# CO2Monitor_V0_3.net
KiCad netlist of a schematic drawn in EAGLE
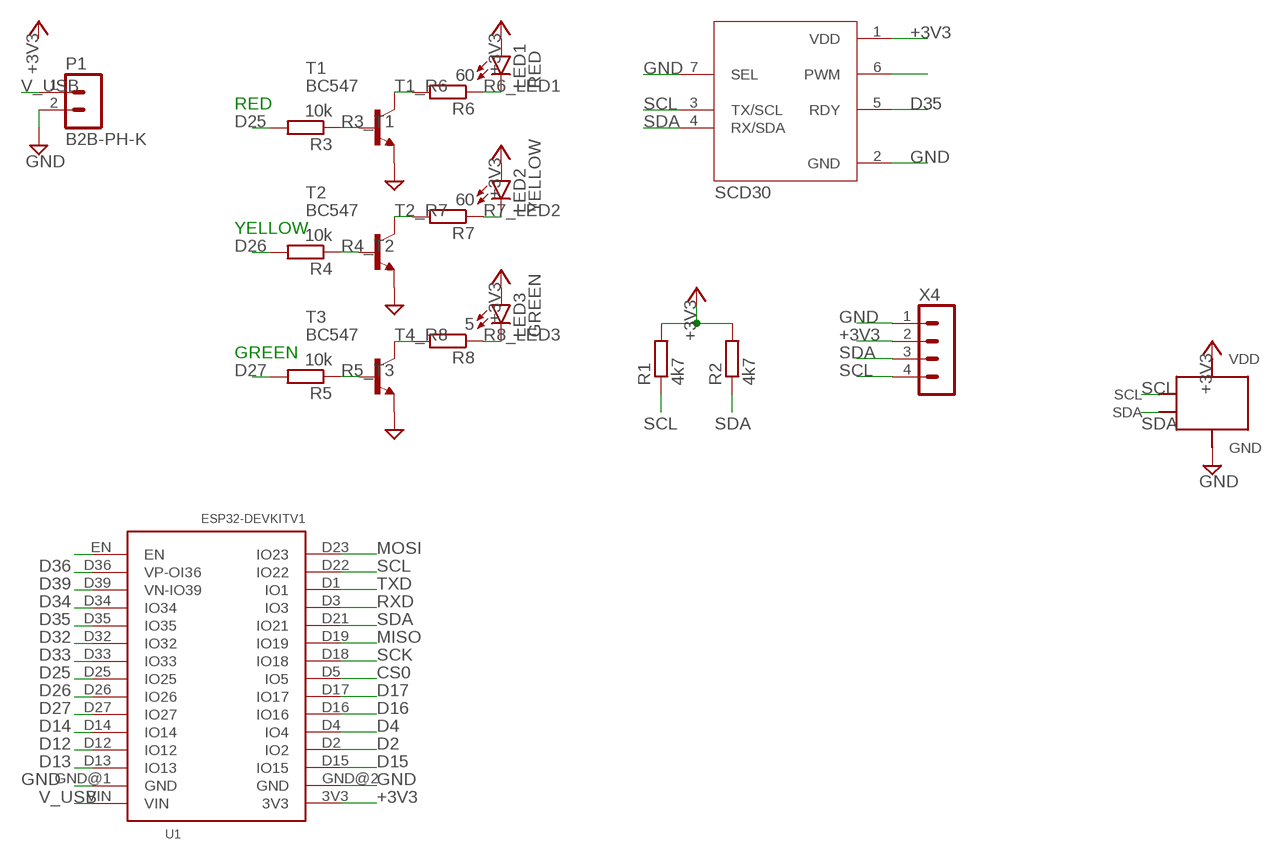
[diagram p0: schematic, sheet 1]

(export (version "E")
  (design (tool "Eeschema 10.0.6"))
  (components
    (comp (ref "LED1")
      (value "RED")
      (footprint "eagle-import:LED5MM")
      (libsource (lib "eagle-import") (part "LED5MM"))
    )
    (comp (ref "LED2")
      (value "YELLOW")
      (footprint "eagle-import:LED5MM")
      (libsource (lib "eagle-import") (part "LED5MM"))
    )
    (comp (ref "LED3")
      (value "GREEN")
      (footprint "eagle-import:LED5MM")
      (libsource (lib "eagle-import") (part "LED5MM"))
    )
    (comp (ref "P1")
      (value "B2B-PH-K")
      (footprint "eagle-import:B2B-PH-K")
      (libsource (lib "eagle-import") (part "B2B-PH-K"))
    )
    (comp (ref "R1")
      (value "4k7")
      (footprint "eagle-import:0207_10")
      (libsource (lib "eagle-import") (part "R-EU_0207/10"))
    )
    (comp (ref "R2")
      (value "4k7")
      (footprint "eagle-import:0207_10")
      (libsource (lib "eagle-import") (part "R-EU_0207/10"))
    )
    (comp (ref "R3")
      (value "10k")
      (footprint "eagle-import:0207_10")
      (libsource (lib "eagle-import") (part "R-EU_0207/10"))
    )
    (comp (ref "R4")
      (value "10k")
      (footprint "eagle-import:0207_10")
      (libsource (lib "eagle-import") (part "R-EU_0207/10"))
    )
    (comp (ref "R5")
      (value "10k")
      (footprint "eagle-import:0207_10")
      (libsource (lib "eagle-import") (part "R-EU_0207/10"))
    )
    (comp (ref "R6")
      (value "60")
      (footprint "eagle-import:0207_10")
      (libsource (lib "eagle-import") (part "R-EU_0207/10"))
    )
    (comp (ref "R7")
      (value "60")
      (footprint "eagle-import:0207_10")
      (libsource (lib "eagle-import") (part "R-EU_0207/10"))
    )
    (comp (ref "R8")
      (value "5")
      (footprint "eagle-import:0207_10")
      (libsource (lib "eagle-import") (part "R-EU_0207/10"))
    )
    (comp (ref "T1")
      (value "BC547")
      (footprint "eagle-import:TO92")
      (libsource (lib "eagle-import") (part "BC547"))
    )
    (comp (ref "T2")
      (value "BC547")
      (footprint "eagle-import:TO92")
      (libsource (lib "eagle-import") (part "BC547"))
    )
    (comp (ref "T3")
      (value "BC547")
      (footprint "eagle-import:TO92")
      (libsource (lib "eagle-import") (part "BC547"))
    )
    (comp (ref "U1")
      (value "ESP32DEVKITV1")
      (footprint "eagle-import:ESP32-DEVKITV1")
      (libsource (lib "eagle-import") (part "ESP32DEVKITV1"))
    )
    (comp (ref "U3")
      (value "SCD30")
      (footprint "eagle-import:MODULE_SCD30")
      (fields (field (name "MF") "Sensirion AG"))
      (libsource (lib "eagle-import") (part "SCD30"))
    )
    (comp (ref "X1")
      (value "1306_0.96\"")
      (footprint "eagle-import:1306_0.96_")
      (libsource (lib "eagle-import") (part "1306_0.96{dblquote}"))
    )
    (comp (ref "X4")
      (value "B4B-PH-K")
      (footprint "eagle-import:B4B-PH-K")
      (libsource (lib "eagle-import") (part "B4B-PH-K"))
    )
  )
  (nets
    (net (code "1") (name "+3V3") (class "Default")
      (node (ref "LED1") (pin "A") (pinfunction "A_A") (pintype "passive"))
      (node (ref "LED2") (pin "A") (pinfunction "A_A") (pintype "passive"))
      (node (ref "LED3") (pin "A") (pinfunction "A_A") (pintype "passive"))
      (node (ref "R1") (pin "2") (pinfunction "2_2") (pintype "passive"))
      (node (ref "R2") (pin "2") (pinfunction "2_2") (pintype "passive"))
      (node (ref "U1") (pin "3V3") (pinfunction "3V3_3V3") (pintype "bidirectional"))
      (node (ref "U3") (pin "1") (pinfunction "VDD_1") (pintype "power_in"))
      (node (ref "X1") (pin "VDD") (pinfunction "VDD_VDD") (pintype "bidirectional"))
      (node (ref "X4") (pin "2") (pinfunction "2_2") (pintype "passive"))
    )
    (net (code "2") (name "/CS0") (class "Default")
      (node (ref "U1") (pin "D5") (pinfunction "IO5_D5") (pintype "bidirectional"))
    )
    (net (code "3") (name "/D2") (class "Default")
      (node (ref "U1") (pin "D2") (pinfunction "IO2_D2") (pintype "bidirectional"))
    )
    (net (code "4") (name "/D4") (class "Default")
      (node (ref "U1") (pin "D4") (pinfunction "IO4_D4") (pintype "bidirectional"))
    )
    (net (code "5") (name "/D12") (class "Default")
      (node (ref "U1") (pin "D12") (pinfunction "IO12_D12") (pintype "bidirectional"))
    )
    (net (code "6") (name "/D13") (class "Default")
      (node (ref "U1") (pin "D13") (pinfunction "IO13_D13") (pintype "bidirectional"))
    )
    (net (code "7") (name "/D14") (class "Default")
      (node (ref "U1") (pin "D14") (pinfunction "IO14_D14") (pintype "bidirectional"))
    )
    (net (code "8") (name "/D15") (class "Default")
      (node (ref "U1") (pin "D15") (pinfunction "IO15_D15") (pintype "bidirectional"))
    )
    (net (code "9") (name "/D16") (class "Default")
      (node (ref "U1") (pin "D16") (pinfunction "IO16_D16") (pintype "bidirectional"))
    )
    (net (code "10") (name "/D17") (class "Default")
      (node (ref "U1") (pin "D17") (pinfunction "IO17_D17") (pintype "bidirectional"))
    )
    (net (code "11") (name "/D25") (class "Default")
      (node (ref "R3") (pin "2") (pinfunction "2_2") (pintype "passive"))
      (node (ref "U1") (pin "D25") (pinfunction "IO25_D25") (pintype "bidirectional"))
    )
    (net (code "12") (name "/D26") (class "Default")
      (node (ref "R4") (pin "2") (pinfunction "2_2") (pintype "passive"))
      (node (ref "U1") (pin "D26") (pinfunction "IO26_D26") (pintype "bidirectional"))
    )
    (net (code "13") (name "/D27") (class "Default")
      (node (ref "R5") (pin "2") (pinfunction "2_2") (pintype "passive"))
      (node (ref "U1") (pin "D27") (pinfunction "IO27_D27") (pintype "bidirectional"))
    )
    (net (code "14") (name "/D32") (class "Default")
      (node (ref "U1") (pin "D32") (pinfunction "IO32_D32") (pintype "bidirectional"))
    )
    (net (code "15") (name "/D33") (class "Default")
      (node (ref "U1") (pin "D33") (pinfunction "IO33_D33") (pintype "bidirectional"))
    )
    (net (code "16") (name "/D34") (class "Default")
      (node (ref "U1") (pin "D34") (pinfunction "IO34_D34") (pintype "bidirectional"))
    )
    (net (code "17") (name "/D35") (class "Default")
      (node (ref "U1") (pin "D35") (pinfunction "IO35_D35") (pintype "bidirectional"))
      (node (ref "U3") (pin "5") (pinfunction "RDY_5") (pintype "bidirectional"))
    )
    (net (code "18") (name "/D36") (class "Default")
      (node (ref "U1") (pin "D36") (pinfunction "VP-OI36_D36") (pintype "bidirectional"))
    )
    (net (code "19") (name "/D39") (class "Default")
      (node (ref "U1") (pin "D39") (pinfunction "VN-IO39_D39") (pintype "bidirectional"))
    )
    (net (code "20") (name "/MISO") (class "Default")
      (node (ref "U1") (pin "D19") (pinfunction "IO19_D19") (pintype "bidirectional"))
    )
    (net (code "21") (name "/MOSI") (class "Default")
      (node (ref "U1") (pin "D23") (pinfunction "IO23_D23") (pintype "bidirectional"))
    )
    (net (code "22") (name "/R3_T1") (class "Default")
      (node (ref "R3") (pin "1") (pinfunction "1_1") (pintype "passive"))
      (node (ref "T1") (pin "2") (pinfunction "B_2") (pintype "passive"))
    )
    (net (code "23") (name "/R4_T2") (class "Default")
      (node (ref "R4") (pin "1") (pinfunction "1_1") (pintype "passive"))
      (node (ref "T2") (pin "2") (pinfunction "B_2") (pintype "passive"))
    )
    (net (code "24") (name "/R5_T3") (class "Default")
      (node (ref "R5") (pin "1") (pinfunction "1_1") (pintype "passive"))
      (node (ref "T3") (pin "2") (pinfunction "B_2") (pintype "passive"))
    )
    (net (code "25") (name "/R6_LED1") (class "Default")
      (node (ref "LED1") (pin "K") (pinfunction "C_K") (pintype "passive"))
      (node (ref "R6") (pin "1") (pinfunction "1_1") (pintype "passive"))
    )
    (net (code "26") (name "/R7_LED2") (class "Default")
      (node (ref "LED2") (pin "K") (pinfunction "C_K") (pintype "passive"))
      (node (ref "R7") (pin "1") (pinfunction "1_1") (pintype "passive"))
    )
    (net (code "27") (name "/R8_LED3") (class "Default")
      (node (ref "LED3") (pin "K") (pinfunction "C_K") (pintype "passive"))
      (node (ref "R8") (pin "1") (pinfunction "1_1") (pintype "passive"))
    )
    (net (code "28") (name "/RXD") (class "Default")
      (node (ref "U1") (pin "D3") (pinfunction "IO3_D3") (pintype "bidirectional"))
    )
    (net (code "29") (name "/SCK") (class "Default")
      (node (ref "U1") (pin "D18") (pinfunction "IO18_D18") (pintype "bidirectional"))
    )
    (net (code "30") (name "/SCL") (class "Default")
      (node (ref "R1") (pin "1") (pinfunction "1_1") (pintype "passive"))
      (node (ref "U1") (pin "D22") (pinfunction "IO22_D22") (pintype "bidirectional"))
      (node (ref "U3") (pin "3") (pinfunction "TX/SCL_3") (pintype "bidirectional"))
      (node (ref "X1") (pin "SCL") (pinfunction "SCL_SCL") (pintype "bidirectional"))
      (node (ref "X4") (pin "4") (pinfunction "4_4") (pintype "passive"))
    )
    (net (code "31") (name "/SDA") (class "Default")
      (node (ref "R2") (pin "1") (pinfunction "1_1") (pintype "passive"))
      (node (ref "U1") (pin "D21") (pinfunction "IO21_D21") (pintype "bidirectional"))
      (node (ref "U3") (pin "4") (pinfunction "RX/SDA_4") (pintype "bidirectional"))
      (node (ref "X1") (pin "SDA") (pinfunction "SDA_SDA") (pintype "bidirectional"))
      (node (ref "X4") (pin "3") (pinfunction "3_3") (pintype "passive"))
    )
    (net (code "32") (name "/T1_R6") (class "Default")
      (node (ref "R6") (pin "2") (pinfunction "2_2") (pintype "passive"))
      (node (ref "T1") (pin "3") (pinfunction "C_3") (pintype "passive"))
    )
    (net (code "33") (name "/T2_R7") (class "Default")
      (node (ref "R7") (pin "2") (pinfunction "2_2") (pintype "passive"))
      (node (ref "T2") (pin "3") (pinfunction "C_3") (pintype "passive"))
    )
    (net (code "34") (name "/T4_R8") (class "Default")
      (node (ref "R8") (pin "2") (pinfunction "2_2") (pintype "passive"))
      (node (ref "T3") (pin "3") (pinfunction "C_3") (pintype "passive"))
    )
    (net (code "35") (name "/TXD") (class "Default")
      (node (ref "U1") (pin "D1") (pinfunction "IO1_D1") (pintype "bidirectional"))
    )
    (net (code "36") (name "/V_USB") (class "Default")
      (node (ref "P1") (pin "1") (pinfunction "1_1") (pintype "passive"))
      (node (ref "U1") (pin "VIN") (pinfunction "VIN_VIN") (pintype "bidirectional"))
    )
    (net (code "37") (name "GND") (class "Default")
      (node (ref "P1") (pin "2") (pinfunction "2_2") (pintype "passive"))
      (node (ref "T1") (pin "1") (pinfunction "E_1") (pintype "passive"))
      (node (ref "T2") (pin "1") (pinfunction "E_1") (pintype "passive"))
      (node (ref "T3") (pin "1") (pinfunction "E_1") (pintype "passive"))
      (node (ref "U1") (pin "GND@1") (pinfunction "GND_GND@1") (pintype "bidirectional"))
      (node (ref "U1") (pin "GND@2") (pinfunction "GND_GND@2") (pintype "bidirectional"))
      (node (ref "U3") (pin "2") (pinfunction "GND_2") (pintype "power_in"))
      (node (ref "U3") (pin "7") (pinfunction "SEL_7") (pintype "input"))
      (node (ref "X1") (pin "GND") (pinfunction "GND_GND") (pintype "bidirectional"))
      (node (ref "X4") (pin "1") (pinfunction "1_1") (pintype "passive"))
    )
    (net (code "38") (name "unconnected-(U1-PadEN)") (class "Default")
      (node (ref "U1") (pin "EN") (pinfunction "EN_EN") (pintype "bidirectional"))
    )
    (net (code "39") (name "unconnected-(U3-PWM-Pad6)") (class "Default")
      (node (ref "U3") (pin "6") (pinfunction "PWM_6") (pintype "output"))
    )
  )
)
